# tiny_thinkpad.net
KiCad netlist of a schematic drawn in EAGLE
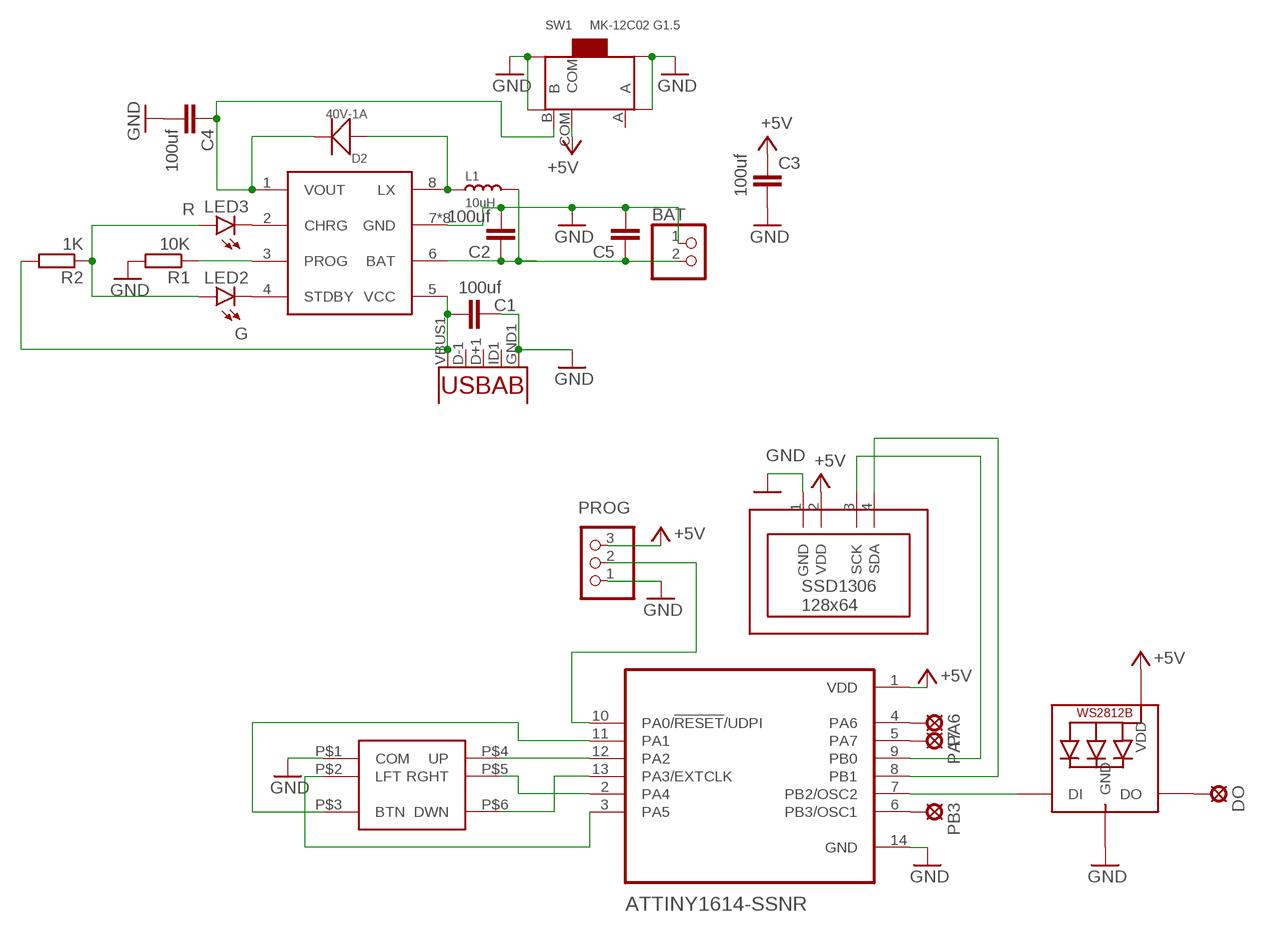
[diagram p0: schematic, sheet 1]

(export (version "E")
  (design (tool "Eeschema 10.0.6"))
  (components
    (comp (ref "AT1614")
      (value "ATTINY1614-SSNR")
      (footprint "eagle-import:SOIC127P600X175-14N")
      (fields (field (name "MF") "Microchip"))
      (libsource (lib "eagle-import") (part "ATTINY1614-SSNR"))
    )
    (comp (ref "BAT")
      (value "PINHD-1X2")
      (footprint "eagle-import:1X02")
      (libsource (lib "eagle-import") (part "PINHD-1X2"))
    )
    (comp (ref "C1")
      (value "100uf")
      (footprint "eagle-import:C1206")
      (libsource (lib "eagle-import") (part "C-EUC1206"))
    )
    (comp (ref "C2")
      (value "100uf")
      (footprint "eagle-import:C1206")
      (libsource (lib "eagle-import") (part "C-EUC1206"))
    )
    (comp (ref "C3")
      (value "100uf")
      (footprint "eagle-import:C1206")
      (libsource (lib "eagle-import") (part "C-EUC1206"))
    )
    (comp (ref "C4")
      (value "100uf")
      (footprint "eagle-import:C1206")
      (libsource (lib "eagle-import") (part "C-EUC1206"))
    )
    (comp (ref "C5")
      (value "100uf")
      (footprint "eagle-import:C1206")
      (libsource (lib "eagle-import") (part "C-EUC1206"))
    )
    (comp (ref "D2")
      (value "40V-1A")
      (footprint "eagle-import:DO-214AC")
      (fields (field (name "MPN") "1N5819"))
      (libsource (lib "eagle-import") (part "SMD-DIODE-SCHOTTKY-40V-1A(DO-214AC)"))
    )
    (comp (ref "DISP")
      (value "SSD1306_128X64_OLEDPINHEAD")
      (footprint "eagle-import:1X04-CLEANBIG")
      (libsource (lib "eagle-import") (part "SSD1306_128X64_OLEDPINHEAD"))
    )
    (comp (ref "DO")
      (value "LSP10")
      (footprint "eagle-import:LSP10")
      (libsource (lib "eagle-import") (part "LSP10"))
    )
    (comp (ref "L1")
      (value "10uH")
      (footprint "eagle-import:L5040S")
      (libsource (lib "eagle-import") (part "SMD-INDUCTOR-10UH-20%-2.35A(2P-5X5X4MM)"))
    )
    (comp (ref "LED1")
      (value "WS2812B5050")
      (footprint "eagle-import:WS2812B")
      (libsource (lib "eagle-import") (part "WS2812B5050"))
    )
    (comp (ref "LED2")
      (value "G")
      (footprint "eagle-import:SML0805")
      (libsource (lib "eagle-import") (part "LEDSML0805"))
    )
    (comp (ref "LED3")
      (value "R")
      (footprint "eagle-import:SML0805")
      (libsource (lib "eagle-import") (part "LEDSML0805"))
    )
    (comp (ref "PA6")
      (value "LSP10")
      (footprint "eagle-import:LSP10")
      (libsource (lib "eagle-import") (part "LSP10"))
    )
    (comp (ref "PA7")
      (value "LSP10")
      (footprint "eagle-import:LSP10")
      (libsource (lib "eagle-import") (part "LSP10"))
    )
    (comp (ref "PB3")
      (value "LSP10")
      (footprint "eagle-import:LSP10")
      (libsource (lib "eagle-import") (part "LSP10"))
    )
    (comp (ref "PROG")
      (value "PINHD-1X3")
      (footprint "eagle-import:1X03")
      (libsource (lib "eagle-import") (part "PINHD-1X3"))
    )
    (comp (ref "R1")
      (value "10K")
      (footprint "eagle-import:R0805")
      (libsource (lib "eagle-import") (part "R-EU_R0805"))
    )
    (comp (ref "R2")
      (value "1K")
      (footprint "eagle-import:R0805")
      (libsource (lib "eagle-import") (part "R-EU_R0805"))
    )
    (comp (ref "SW1")
      (value "MK-12C02 G1.5")
      (footprint "eagle-import:SW7-SMD-L6.7X2.7X3.2MM")
      (libsource (lib "eagle-import") (part "SMD-TOGGLE-SWITCH-ON-ON(3+4P-6.7X2.7MM)"))
    )
    (comp (ref "U$3")
      (value "TP5400")
      (footprint "eagle-import:SOP-8")
      (libsource (lib "eagle-import") (part "TP5400"))
    )
    (comp (ref "U$4")
      (value "5WAY_SMD_SWITCH")
      (footprint "eagle-import:SUNROM_5WAY_SMD_SWITCH")
      (libsource (lib "eagle-import") (part "5WAY_SMD_SWITCH"))
    )
    (comp (ref "U2")
      (value "USB-THROUGH")
      (footprint "eagle-import:USB-MICRO-THROUGH")
      (libsource (lib "eagle-import") (part "USB-THROUGH"))
    )
  )
  (nets
    (net (code "1") (name "+5V") (class "Default")
      (node (ref "AT1614") (pin "1") (pinfunction "VDD_1") (pintype "power_in"))
      (node (ref "C3") (pin "1") (pinfunction "1_1") (pintype "passive"))
      (node (ref "DISP") (pin "2") (pinfunction "VDD_2") (pintype "bidirectional"))
      (node (ref "LED1") (pin "1-VDD") (pinfunction "VDD_1-VDD") (pintype "power_in"))
      (node (ref "PROG") (pin "3") (pinfunction "3_3") (pintype "passive"))
      (node (ref "SW1") (pin "COM") (pinfunction "COM_COM") (pintype "bidirectional"))
    )
    (net (code "2") (name "GND") (class "Default")
      (node (ref "AT1614") (pin "14") (pinfunction "GND_14") (pintype "power_in"))
      (node (ref "BAT") (pin "1") (pinfunction "1_1") (pintype "passive"))
      (node (ref "C1") (pin "1") (pinfunction "1_1") (pintype "passive"))
      (node (ref "C2") (pin "2") (pinfunction "2_2") (pintype "passive"))
      (node (ref "C3") (pin "2") (pinfunction "2_2") (pintype "passive"))
      (node (ref "C4") (pin "2") (pinfunction "2_2") (pintype "passive"))
      (node (ref "C5") (pin "2") (pinfunction "2_2") (pintype "passive"))
      (node (ref "DISP") (pin "1") (pinfunction "GND_1") (pintype "bidirectional"))
      (node (ref "LED1") (pin "3-GND") (pinfunction "GND_3-GND") (pintype "power_in"))
      (node (ref "PROG") (pin "1") (pinfunction "1_1") (pintype "passive"))
      (node (ref "R1") (pin "2") (pinfunction "2_2") (pintype "passive"))
      (node (ref "SW1") (pin "SS1") (pinfunction "SS1_SS1") (pintype "bidirectional"))
      (node (ref "SW1") (pin "SS2") (pinfunction "SS2_SS2") (pintype "bidirectional"))
      (node (ref "SW1") (pin "SS3") (pinfunction "SS3_SS3") (pintype "bidirectional"))
      (node (ref "SW1") (pin "SS4") (pinfunction "SS4_SS4") (pintype "bidirectional"))
      (node (ref "U$3") (pin "7") (pinfunction "GND_7") (pintype "bidirectional"))
      (node (ref "U$3") (pin "BOTTOM") (pinfunction "GND_BOTTOM") (pintype "bidirectional"))
      (node (ref "U$3") (pin "P$1") (pinfunction "GND_P$1") (pintype "bidirectional"))
      (node (ref "U$3") (pin "P$2") (pinfunction "GND_P$2") (pintype "bidirectional"))
      (node (ref "U$3") (pin "P$3") (pinfunction "GND_P$3") (pintype "bidirectional"))
      (node (ref "U$3") (pin "P$4") (pinfunction "GND_P$4") (pintype "bidirectional"))
      (node (ref "U$3") (pin "P$5") (pinfunction "GND_P$5") (pintype "bidirectional"))
      (node (ref "U$3") (pin "P$6") (pinfunction "GND_P$6") (pintype "bidirectional"))
      (node (ref "U$4") (pin "P$1") (pinfunction "COM_P$1") (pintype "bidirectional"))
      (node (ref "U2") (pin "GND1") (pinfunction "GND_GND1") (pintype "bidirectional"))
    )
    (net (code "3") (name "Net-(AT1614-PA0{slash}~{RESET}{slash}UDPI)") (class "Default")
      (node (ref "AT1614") (pin "10") (pinfunction "PA0/~{RESET}/UDPI_10") (pintype "bidirectional"))
      (node (ref "PROG") (pin "2") (pinfunction "2_2") (pintype "passive"))
    )
    (net (code "4") (name "Net-(AT1614-PA1)") (class "Default")
      (node (ref "AT1614") (pin "11") (pinfunction "PA1_11") (pintype "bidirectional"))
      (node (ref "U$4") (pin "P$3") (pinfunction "BTN_P$3") (pintype "bidirectional"))
    )
    (net (code "5") (name "Net-(AT1614-PA2)") (class "Default")
      (node (ref "AT1614") (pin "12") (pinfunction "PA2_12") (pintype "bidirectional"))
      (node (ref "U$4") (pin "P$4") (pinfunction "UP_P$4") (pintype "bidirectional"))
    )
    (net (code "6") (name "Net-(AT1614-PA3{slash}EXTCLK)") (class "Default")
      (node (ref "AT1614") (pin "13") (pinfunction "PA3/EXTCLK_13") (pintype "bidirectional"))
      (node (ref "U$4") (pin "P$6") (pinfunction "DWN_P$6") (pintype "bidirectional"))
    )
    (net (code "7") (name "Net-(AT1614-PA4)") (class "Default")
      (node (ref "AT1614") (pin "2") (pinfunction "PA4_2") (pintype "bidirectional"))
      (node (ref "U$4") (pin "P$5") (pinfunction "RGHT_P$5") (pintype "bidirectional"))
    )
    (net (code "8") (name "Net-(AT1614-PA5)") (class "Default")
      (node (ref "AT1614") (pin "3") (pinfunction "PA5_3") (pintype "bidirectional"))
      (node (ref "U$4") (pin "P$2") (pinfunction "LFT_P$2") (pintype "bidirectional"))
    )
    (net (code "9") (name "Net-(AT1614-PA6)") (class "Default")
      (node (ref "AT1614") (pin "4") (pinfunction "PA6_4") (pintype "bidirectional"))
      (node (ref "PA6") (pin "MP") (pinfunction "MP_MP") (pintype "passive"))
    )
    (net (code "10") (name "Net-(AT1614-PA7)") (class "Default")
      (node (ref "AT1614") (pin "5") (pinfunction "PA7_5") (pintype "bidirectional"))
      (node (ref "PA7") (pin "MP") (pinfunction "MP_MP") (pintype "passive"))
    )
    (net (code "11") (name "Net-(AT1614-PB0)") (class "Default")
      (node (ref "AT1614") (pin "9") (pinfunction "PB0_9") (pintype "bidirectional"))
      (node (ref "DISP") (pin "3") (pinfunction "SCK_3") (pintype "bidirectional"))
    )
    (net (code "12") (name "Net-(AT1614-PB1)") (class "Default")
      (node (ref "AT1614") (pin "8") (pinfunction "PB1_8") (pintype "bidirectional"))
      (node (ref "DISP") (pin "4") (pinfunction "SDA_4") (pintype "bidirectional"))
    )
    (net (code "13") (name "Net-(AT1614-PB2{slash}OSC2)") (class "Default")
      (node (ref "AT1614") (pin "7") (pinfunction "PB2/OSC2_7") (pintype "bidirectional"))
      (node (ref "LED1") (pin "4-DIN") (pinfunction "DI_4-DIN") (pintype "input"))
    )
    (net (code "14") (name "Net-(AT1614-PB3{slash}OSC1)") (class "Default")
      (node (ref "AT1614") (pin "6") (pinfunction "PB3/OSC1_6") (pintype "bidirectional"))
      (node (ref "PB3") (pin "MP") (pinfunction "MP_MP") (pintype "passive"))
    )
    (net (code "15") (name "Net-(D2-+)") (class "Default")
      (node (ref "D2") (pin "1") (pinfunction "+_1") (pintype "passive"))
      (node (ref "L1") (pin "1") (pinfunction "1_1") (pintype "passive"))
      (node (ref "U$3") (pin "8") (pinfunction "LX_8") (pintype "bidirectional"))
    )
    (net (code "16") (name "Net-(D2--)") (class "Default")
      (node (ref "C4") (pin "1") (pinfunction "1_1") (pintype "passive"))
      (node (ref "D2") (pin "2") (pinfunction "-_2") (pintype "passive"))
      (node (ref "SW1") (pin "B") (pinfunction "B_B") (pintype "bidirectional"))
      (node (ref "U$3") (pin "1") (pinfunction "VOUT_1") (pintype "bidirectional"))
    )
    (net (code "17") (name "Net-(LED1-DO)") (class "Default")
      (node (ref "DO") (pin "MP") (pinfunction "MP_MP") (pintype "passive"))
      (node (ref "LED1") (pin "2-DOUT") (pinfunction "DO_2-DOUT") (pintype "output"))
    )
    (net (code "18") (name "Net-(LED2-PadA)") (class "Default")
      (node (ref "LED2") (pin "A") (pinfunction "A_A") (pintype "passive"))
      (node (ref "LED3") (pin "A") (pinfunction "A_A") (pintype "passive"))
      (node (ref "R2") (pin "1") (pinfunction "1_1") (pintype "passive"))
    )
    (net (code "19") (name "Net-(U$3-BAT)") (class "Default")
      (node (ref "BAT") (pin "2") (pinfunction "2_2") (pintype "passive"))
      (node (ref "C2") (pin "1") (pinfunction "1_1") (pintype "passive"))
      (node (ref "C5") (pin "1") (pinfunction "1_1") (pintype "passive"))
      (node (ref "L1") (pin "2") (pinfunction "2_2") (pintype "passive"))
      (node (ref "U$3") (pin "6") (pinfunction "BAT_6") (pintype "bidirectional"))
    )
    (net (code "20") (name "Net-(U$3-CHRG)") (class "Default")
      (node (ref "LED3") (pin "C") (pinfunction "C_C") (pintype "passive"))
      (node (ref "U$3") (pin "2") (pinfunction "CHRG_2") (pintype "bidirectional"))
    )
    (net (code "21") (name "Net-(U$3-PROG)") (class "Default")
      (node (ref "R1") (pin "1") (pinfunction "1_1") (pintype "passive"))
      (node (ref "U$3") (pin "3") (pinfunction "PROG_3") (pintype "bidirectional"))
    )
    (net (code "22") (name "Net-(U$3-STDBY)") (class "Default")
      (node (ref "LED2") (pin "C") (pinfunction "C_C") (pintype "passive"))
      (node (ref "U$3") (pin "4") (pinfunction "STDBY_4") (pintype "bidirectional"))
    )
    (net (code "23") (name "Net-(U$3-VCC)") (class "Default")
      (node (ref "C1") (pin "2") (pinfunction "2_2") (pintype "passive"))
      (node (ref "R2") (pin "2") (pinfunction "2_2") (pintype "passive"))
      (node (ref "U$3") (pin "5") (pinfunction "VCC_5") (pintype "bidirectional"))
      (node (ref "U2") (pin "VBUS1") (pinfunction "VBUS_VBUS1") (pintype "bidirectional"))
    )
    (net (code "24") (name "unconnected-(SW1-PadA)") (class "Default")
      (node (ref "SW1") (pin "A") (pinfunction "A_A") (pintype "bidirectional"))
    )
    (net (code "25") (name "unconnected-(U2-D+-PadD+1)") (class "Default")
      (node (ref "U2") (pin "D+1") (pinfunction "D+_D+1") (pintype "bidirectional"))
    )
    (net (code "26") (name "unconnected-(U2-D--PadD-1)") (class "Default")
      (node (ref "U2") (pin "D-1") (pinfunction "D-_D-1") (pintype "bidirectional"))
    )
    (net (code "27") (name "unconnected-(U2-USBID-PadID1)") (class "Default")
      (node (ref "U2") (pin "ID1") (pinfunction "USBID_ID1") (pintype "bidirectional"))
    )
  )
)
